# ConverterBoardRev2.net
KiCad netlist of a schematic drawn in EAGLE
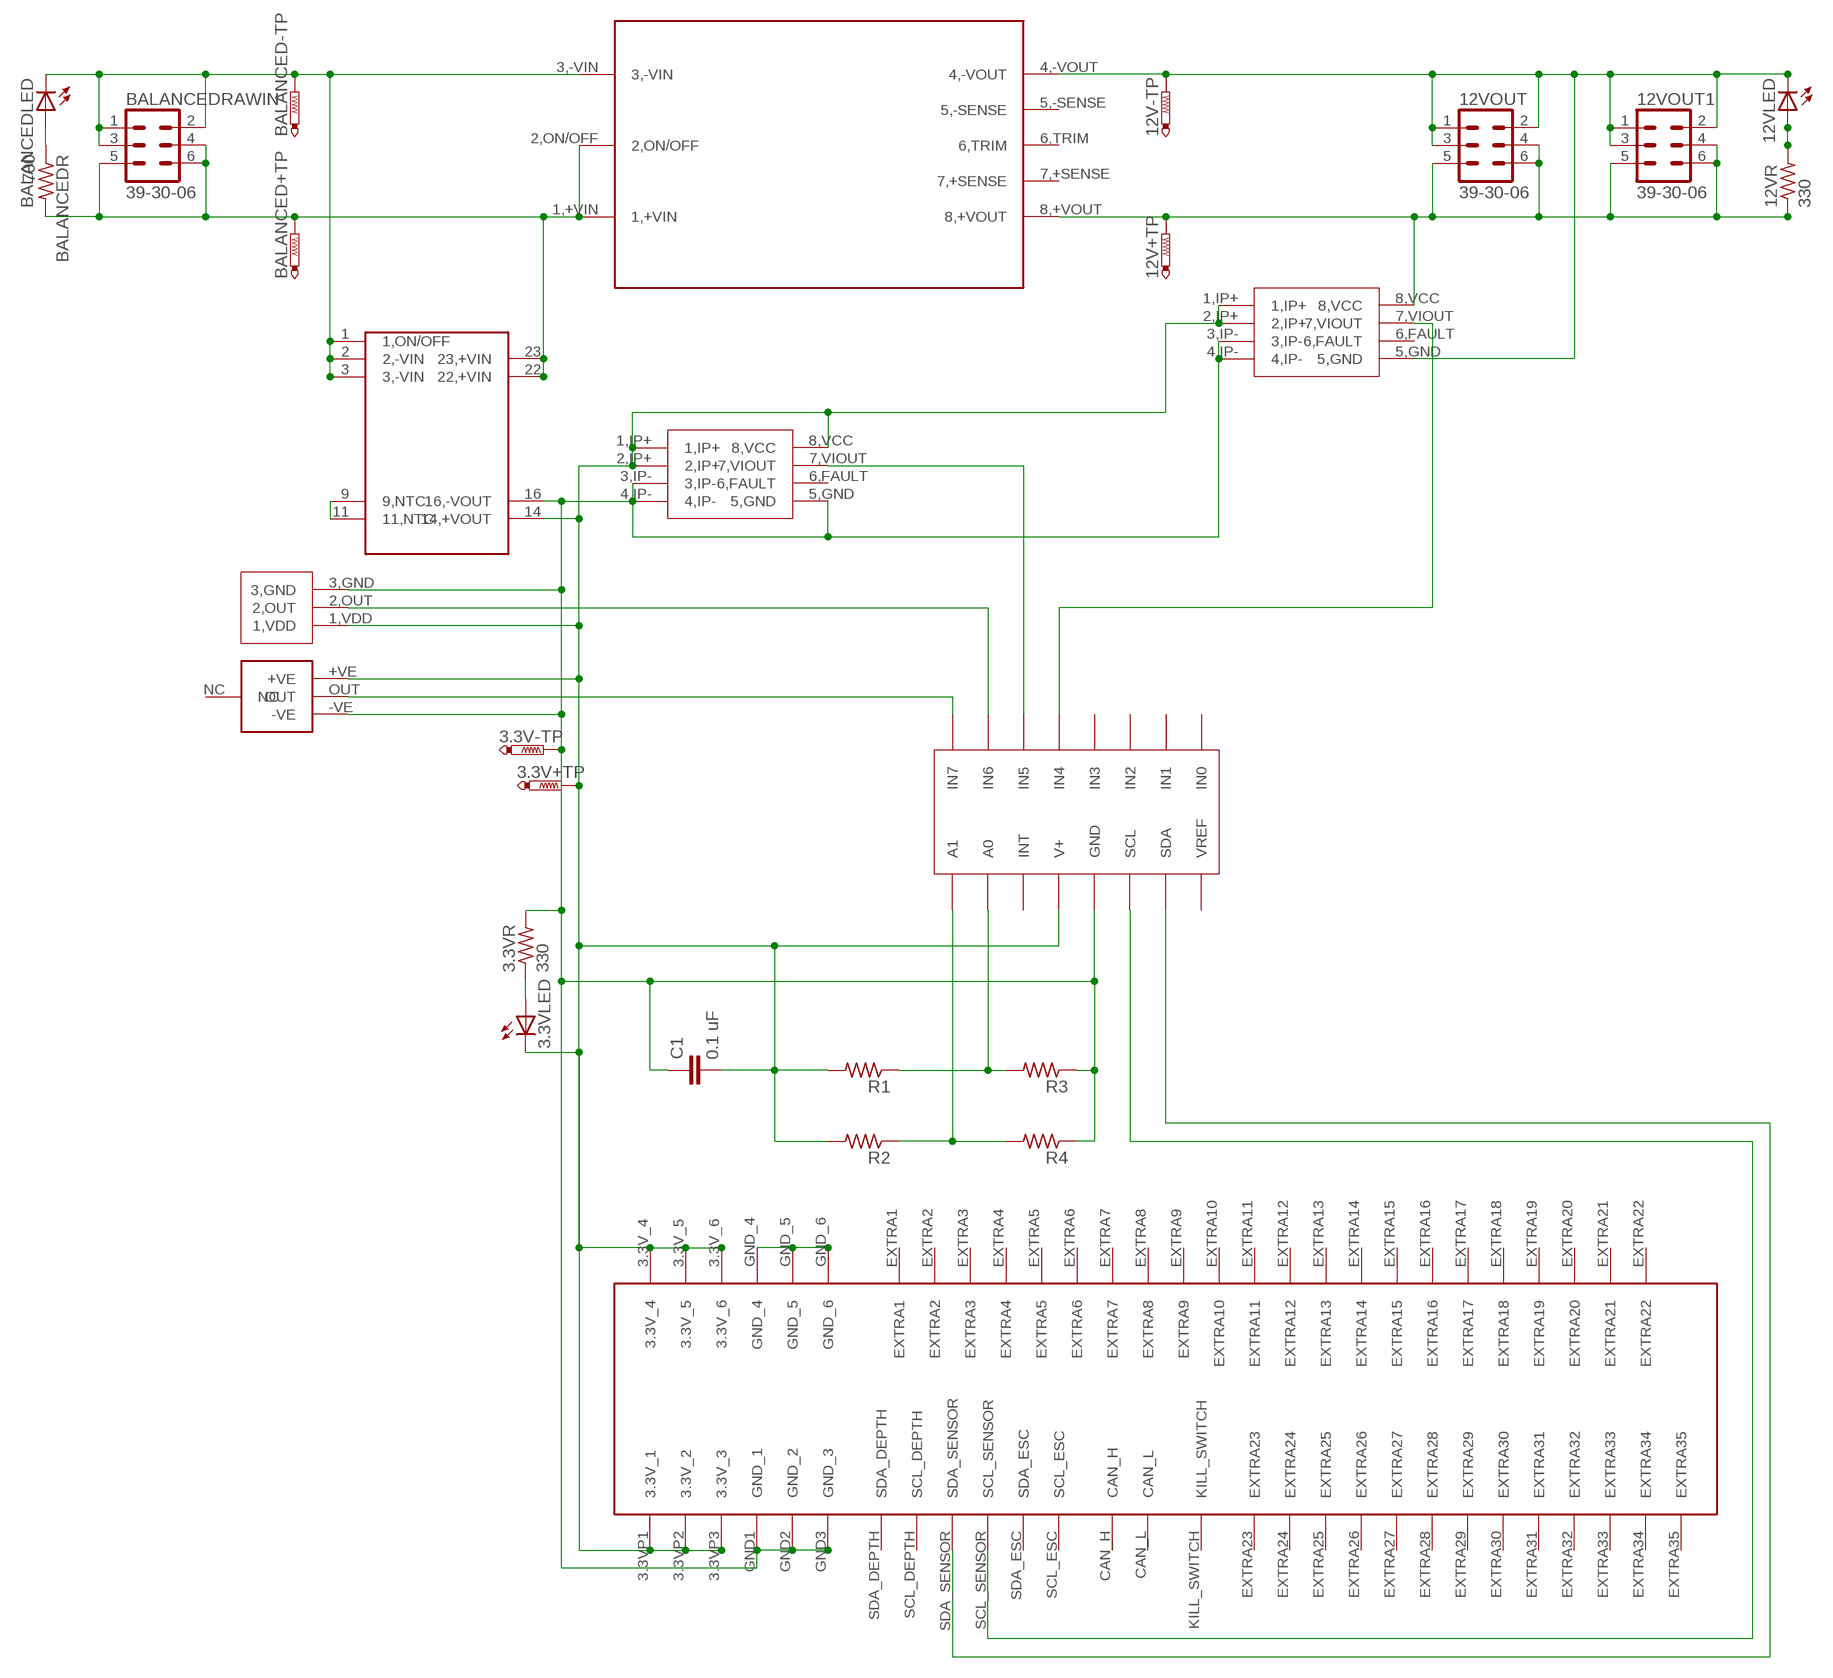
[diagram p0: schematic, sheet 1]

(export (version "E")
  (design (tool "Eeschema 10.0.6"))
  (components
    (comp (ref "3.3V+TP")
      (value "PTR1B1,27")
      (footprint "eagle-import:B1,27")
      (libsource (lib "eagle-import") (part "PTR1B1,27"))
    )
    (comp (ref "3.3V-TP")
      (value "PTR1B1,27")
      (footprint "eagle-import:B1,27")
      (libsource (lib "eagle-import") (part "PTR1B1,27"))
    )
    (comp (ref "3.3VLED")
      (value "LTST-S270GKT")
      (footprint "eagle-import:LTST-S270GKT")
      (libsource (lib "eagle-import") (part "LTST-S270GKT"))
    )
    (comp (ref "3.3VR")
      (value "330")
      (footprint "eagle-import:0204_7")
      (libsource (lib "eagle-import") (part "R-US_0204/7"))
    )
    (comp (ref "12V+TP")
      (value "PTR1B1,27")
      (footprint "eagle-import:B1,27")
      (libsource (lib "eagle-import") (part "PTR1B1,27"))
    )
    (comp (ref "12V-TP")
      (value "PTR1B1,27")
      (footprint "eagle-import:B1,27")
      (libsource (lib "eagle-import") (part "PTR1B1,27"))
    )
    (comp (ref "12VLED")
      (value "LTST-S270GKT")
      (footprint "eagle-import:LTST-S270GKT")
      (libsource (lib "eagle-import") (part "LTST-S270GKT"))
    )
    (comp (ref "12VOUT")
      (value "39-30-06")
      (footprint "eagle-import:39-30-_06_")
      (libsource (lib "eagle-import") (part "39-30-?06?"))
    )
    (comp (ref "12VOUT1")
      (value "39-30-06")
      (footprint "eagle-import:39-30-_06_")
      (libsource (lib "eagle-import") (part "39-30-?06?"))
    )
    (comp (ref "12VR")
      (value "330")
      (footprint "eagle-import:0204_7")
      (libsource (lib "eagle-import") (part "R-US_0204/7"))
    )
    (comp (ref "BALANCED+TP")
      (value "PTR1B1,27")
      (footprint "eagle-import:B1,27")
      (libsource (lib "eagle-import") (part "PTR1B1,27"))
    )
    (comp (ref "BALANCED-TP")
      (value "PTR1B1,27")
      (footprint "eagle-import:B1,27")
      (libsource (lib "eagle-import") (part "PTR1B1,27"))
    )
    (comp (ref "BALANCEDLED")
      (value "LTST-S270GKT")
      (footprint "eagle-import:LTST-S270GKT")
      (libsource (lib "eagle-import") (part "LTST-S270GKT"))
    )
    (comp (ref "BALANCEDR")
      (value "700")
      (footprint "eagle-import:0204_7")
      (libsource (lib "eagle-import") (part "R-US_0204/7"))
    )
    (comp (ref "BALANCEDRAWIN")
      (value "39-30-06")
      (footprint "eagle-import:39-30-_06_")
      (libsource (lib "eagle-import") (part "39-30-?06?"))
    )
    (comp (ref "C1")
      (value "0.1 uF")
      (footprint "eagle-import:C025-024X044")
      (libsource (lib "eagle-import") (part "C-EU025-024X044"))
    )
    (comp (ref "R1")
      (value "R-US_0204/7")
      (footprint "eagle-import:0204_7")
      (libsource (lib "eagle-import") (part "R-US_0204/7"))
    )
    (comp (ref "R2")
      (value "R-US_0204/7")
      (footprint "eagle-import:0204_7")
      (libsource (lib "eagle-import") (part "R-US_0204/7"))
    )
    (comp (ref "R3")
      (value "R-US_0204/7")
      (footprint "eagle-import:0204_7")
      (libsource (lib "eagle-import") (part "R-US_0204/7"))
    )
    (comp (ref "R4")
      (value "R-US_0204/7")
      (footprint "eagle-import:0204_7")
      (libsource (lib "eagle-import") (part "R-US_0204/7"))
    )
    (comp (ref "U$1")
      (value "12VCONV")
      (footprint "eagle-import:12VCONV")
      (libsource (lib "eagle-import") (part "12VCONV"))
    )
    (comp (ref "U$2")
      (value "3.3VCONV")
      (footprint "eagle-import:3.3VCONV")
      (libsource (lib "eagle-import") (part "3.3VCONV"))
    )
    (comp (ref "U$3")
      (value "5530843")
      (footprint "eagle-import:5530843-6-BOARDFINGERS")
      (libsource (lib "eagle-import") (part "5530843"))
    )
    (comp (ref "U$4")
      (value "CURRENTSENS")
      (footprint "eagle-import:CURRENTSENS")
      (libsource (lib "eagle-import") (part "CURRENTSENS"))
    )
    (comp (ref "U$5")
      (value "CURRENTSENS")
      (footprint "eagle-import:CURRENTSENS")
      (libsource (lib "eagle-import") (part "CURRENTSENS"))
    )
    (comp (ref "U$6")
      (value "HUMIDITYSENSOR")
      (footprint "eagle-import:HUMIDITYSENSOR")
      (libsource (lib "eagle-import") (part "HUMIDITYSENSOR"))
    )
    (comp (ref "U$7")
      (value "TEMPSENS")
      (footprint "eagle-import:TEMPSENS")
      (libsource (lib "eagle-import") (part "TEMPSENS"))
    )
    (comp (ref "U$8")
      (value "ADC128D818")
      (footprint "eagle-import:TSSOP-16")
      (libsource (lib "eagle-import") (part "ADC128D818"))
    )
  )
  (nets
    (net (code "1") (name "Net-(3.3VLED-A)") (class "Default")
      (node (ref "3.3VLED") (pin "ANODE") (pinfunction "A_ANODE") (pintype "passive"))
      (node (ref "3.3VR") (pin "1") (pinfunction "1_1") (pintype "passive"))
    )
    (net (code "2") (name "Net-(3.3VLED-C)") (class "Default")
      (node (ref "3.3V+TP") (pin "TP") (pinfunction "TP_TP") (pintype "input"))
      (node (ref "3.3VLED") (pin "CATHODE") (pinfunction "C_CATHODE") (pintype "passive"))
      (node (ref "C1") (pin "2") (pinfunction "2_2") (pintype "passive"))
      (node (ref "R1") (pin "2") (pinfunction "2_2") (pintype "passive"))
      (node (ref "R2") (pin "2") (pinfunction "2_2") (pintype "passive"))
      (node (ref "U$2") (pin "14") (pinfunction "14,+VOUT_14") (pintype "bidirectional"))
      (node (ref "U$3") (pin "3.3VP1") (pinfunction "3.3V_1_3.3VP1") (pintype "bidirectional"))
      (node (ref "U$3") (pin "3.3VP2") (pinfunction "3.3V_2_3.3VP2") (pintype "bidirectional"))
      (node (ref "U$3") (pin "3.3VP3") (pinfunction "3.3V_3_3.3VP3") (pintype "bidirectional"))
      (node (ref "U$3") (pin "3.3V_4") (pinfunction "3.3V_4_3.3V_4") (pintype "bidirectional"))
      (node (ref "U$3") (pin "3.3V_5") (pinfunction "3.3V_5_3.3V_5") (pintype "bidirectional"))
      (node (ref "U$3") (pin "3.3V_6") (pinfunction "3.3V_6_3.3V_6") (pintype "bidirectional"))
      (node (ref "U$4") (pin "1,IP+") (pinfunction "1,IP+_1,IP+") (pintype "bidirectional"))
      (node (ref "U$4") (pin "2,IP+") (pinfunction "2,IP+_2,IP+") (pintype "bidirectional"))
      (node (ref "U$5") (pin "1,IP+") (pinfunction "1,IP+_1,IP+") (pintype "bidirectional"))
      (node (ref "U$5") (pin "2,IP+") (pinfunction "2,IP+_2,IP+") (pintype "bidirectional"))
      (node (ref "U$5") (pin "8,VCC") (pinfunction "8,VCC_8,VCC") (pintype "bidirectional"))
      (node (ref "U$6") (pin "+VE") (pinfunction "+VE_+VE") (pintype "bidirectional"))
      (node (ref "U$7") (pin "1,VDD") (pinfunction "1,VDD_1,VDD") (pintype "bidirectional"))
      (node (ref "U$8") (pin "V+") (pinfunction "V+_V+") (pintype "bidirectional"))
    )
    (net (code "3") (name "Net-(12V+TP-PadTP)") (class "Default")
      (node (ref "12V+TP") (pin "TP") (pinfunction "TP_TP") (pintype "input"))
      (node (ref "12VOUT") (pin "4") (pinfunction "4_4") (pintype "passive"))
      (node (ref "12VOUT") (pin "5") (pinfunction "5_5") (pintype "passive"))
      (node (ref "12VOUT") (pin "6") (pinfunction "6_6") (pintype "passive"))
      (node (ref "12VOUT1") (pin "4") (pinfunction "4_4") (pintype "passive"))
      (node (ref "12VOUT1") (pin "5") (pinfunction "5_5") (pintype "passive"))
      (node (ref "12VOUT1") (pin "6") (pinfunction "6_6") (pintype "passive"))
      (node (ref "12VR") (pin "1") (pinfunction "1_1") (pintype "passive"))
      (node (ref "U$1") (pin "8,+VOUT") (pinfunction "8,+VOUT_8,+VOUT") (pintype "bidirectional"))
      (node (ref "U$4") (pin "8,VCC") (pinfunction "8,VCC_8,VCC") (pintype "bidirectional"))
    )
    (net (code "4") (name "Net-(12VLED-A)") (class "Default")
      (node (ref "12VLED") (pin "ANODE") (pinfunction "A_ANODE") (pintype "passive"))
      (node (ref "12VR") (pin "2") (pinfunction "2_2") (pintype "passive"))
    )
    (net (code "5") (name "Net-(12VLED-C)") (class "Default")
      (node (ref "12V-TP") (pin "TP") (pinfunction "TP_TP") (pintype "input"))
      (node (ref "12VLED") (pin "CATHODE") (pinfunction "C_CATHODE") (pintype "passive"))
      (node (ref "12VOUT") (pin "1") (pinfunction "1_1") (pintype "passive"))
      (node (ref "12VOUT") (pin "2") (pinfunction "2_2") (pintype "passive"))
      (node (ref "12VOUT") (pin "3") (pinfunction "3_3") (pintype "passive"))
      (node (ref "12VOUT1") (pin "1") (pinfunction "1_1") (pintype "passive"))
      (node (ref "12VOUT1") (pin "2") (pinfunction "2_2") (pintype "passive"))
      (node (ref "12VOUT1") (pin "3") (pinfunction "3_3") (pintype "passive"))
      (node (ref "U$1") (pin "4,-VOUT") (pinfunction "4,-VOUT_4,-VOUT") (pintype "bidirectional"))
      (node (ref "U$4") (pin "5,GND") (pinfunction "5,GND_5,GND") (pintype "bidirectional"))
    )
    (net (code "6") (name "Net-(BALANCEDLED-A)") (class "Default")
      (node (ref "BALANCEDLED") (pin "ANODE") (pinfunction "A_ANODE") (pintype "passive"))
      (node (ref "BALANCEDR") (pin "1") (pinfunction "1_1") (pintype "passive"))
    )
    (net (code "7") (name "Net-(BALANCEDLED-C)") (class "Default")
      (node (ref "BALANCED-TP") (pin "TP") (pinfunction "TP_TP") (pintype "input"))
      (node (ref "BALANCEDLED") (pin "CATHODE") (pinfunction "C_CATHODE") (pintype "passive"))
      (node (ref "BALANCEDRAWIN") (pin "1") (pinfunction "1_1") (pintype "passive"))
      (node (ref "BALANCEDRAWIN") (pin "2") (pinfunction "2_2") (pintype "passive"))
      (node (ref "BALANCEDRAWIN") (pin "3") (pinfunction "3_3") (pintype "passive"))
      (node (ref "U$1") (pin "3,-VIN") (pinfunction "3,-VIN_3,-VIN") (pintype "bidirectional"))
      (node (ref "U$2") (pin "1") (pinfunction "1,ON/OFF_1") (pintype "bidirectional"))
      (node (ref "U$2") (pin "2") (pinfunction "2,-VIN_2") (pintype "bidirectional"))
      (node (ref "U$2") (pin "3") (pinfunction "3,-VIN_3") (pintype "bidirectional"))
    )
    (net (code "8") (name "Net-(R1-Pad1)") (class "Default")
      (node (ref "R1") (pin "1") (pinfunction "1_1") (pintype "passive"))
      (node (ref "R3") (pin "2") (pinfunction "2_2") (pintype "passive"))
      (node (ref "U$8") (pin "A0") (pinfunction "A0_A0") (pintype "bidirectional"))
    )
    (net (code "9") (name "Net-(R2-Pad1)") (class "Default")
      (node (ref "R2") (pin "1") (pinfunction "1_1") (pintype "passive"))
      (node (ref "R4") (pin "2") (pinfunction "2_2") (pintype "passive"))
      (node (ref "U$8") (pin "A1") (pinfunction "A1_A1") (pintype "bidirectional"))
    )
    (net (code "10") (name "Net-(U$2-11,NTC)") (class "Default")
      (node (ref "U$2") (pin "11") (pinfunction "11,NTC_11") (pintype "bidirectional"))
      (node (ref "U$2") (pin "9") (pinfunction "9,NTC_9") (pintype "bidirectional"))
    )
    (net (code "11") (name "Net-(U$2-16,-VOUT)") (class "Default")
      (node (ref "3.3V-TP") (pin "TP") (pinfunction "TP_TP") (pintype "input"))
      (node (ref "3.3VR") (pin "2") (pinfunction "2_2") (pintype "passive"))
      (node (ref "C1") (pin "1") (pinfunction "1_1") (pintype "passive"))
      (node (ref "R3") (pin "1") (pinfunction "1_1") (pintype "passive"))
      (node (ref "R4") (pin "1") (pinfunction "1_1") (pintype "passive"))
      (node (ref "U$2") (pin "16") (pinfunction "16,-VOUT_16") (pintype "bidirectional"))
      (node (ref "U$3") (pin "GND1") (pinfunction "GND_1_GND1") (pintype "bidirectional"))
      (node (ref "U$3") (pin "GND2") (pinfunction "GND_2_GND2") (pintype "bidirectional"))
      (node (ref "U$3") (pin "GND3") (pinfunction "GND_3_GND3") (pintype "bidirectional"))
      (node (ref "U$4") (pin "3,IP-") (pinfunction "3,IP-_3,IP-") (pintype "bidirectional"))
      (node (ref "U$4") (pin "4,IP-") (pinfunction "4,IP-_4,IP-") (pintype "bidirectional"))
      (node (ref "U$5") (pin "3,IP-") (pinfunction "3,IP-_3,IP-") (pintype "bidirectional"))
      (node (ref "U$5") (pin "4,IP-") (pinfunction "4,IP-_4,IP-") (pintype "bidirectional"))
      (node (ref "U$5") (pin "5,GND") (pinfunction "5,GND_5,GND") (pintype "bidirectional"))
      (node (ref "U$6") (pin "-VE") (pinfunction "-VE_-VE") (pintype "bidirectional"))
      (node (ref "U$7") (pin "3,GND") (pinfunction "3,GND_3,GND") (pintype "bidirectional"))
      (node (ref "U$8") (pin "GND") (pinfunction "GND_GND") (pintype "bidirectional"))
    )
    (net (code "12") (name "Net-(U$2-22,+VIN)") (class "Default")
      (node (ref "BALANCED+TP") (pin "TP") (pinfunction "TP_TP") (pintype "input"))
      (node (ref "BALANCEDR") (pin "2") (pinfunction "2_2") (pintype "passive"))
      (node (ref "BALANCEDRAWIN") (pin "4") (pinfunction "4_4") (pintype "passive"))
      (node (ref "BALANCEDRAWIN") (pin "5") (pinfunction "5_5") (pintype "passive"))
      (node (ref "BALANCEDRAWIN") (pin "6") (pinfunction "6_6") (pintype "passive"))
      (node (ref "U$1") (pin "1,+VIN") (pinfunction "1,+VIN_1,+VIN") (pintype "bidirectional"))
      (node (ref "U$1") (pin "2,ON/OFF") (pinfunction "2,ON/OFF_2,ON/OFF") (pintype "bidirectional"))
      (node (ref "U$2") (pin "22") (pinfunction "22,+VIN_22") (pintype "bidirectional"))
      (node (ref "U$2") (pin "23") (pinfunction "23,+VIN_23") (pintype "bidirectional"))
    )
    (net (code "13") (name "Net-(U$3-PadGND_4)") (class "Default")
      (node (ref "U$3") (pin "GND_4") (pinfunction "GND_4_GND_4") (pintype "bidirectional"))
      (node (ref "U$3") (pin "GND_5") (pinfunction "GND_5_GND_5") (pintype "bidirectional"))
      (node (ref "U$3") (pin "GND_6") (pinfunction "GND_6_GND_6") (pintype "bidirectional"))
    )
    (net (code "14") (name "Net-(U$3-PadSCL_SENSOR)") (class "Default")
      (node (ref "U$3") (pin "SCL_SENSOR") (pinfunction "SCL_SENSOR_SCL_SENSOR") (pintype "bidirectional"))
      (node (ref "U$8") (pin "SCL") (pinfunction "SCL_SCL") (pintype "bidirectional"))
    )
    (net (code "15") (name "Net-(U$3-PadSDA_SENSOR)") (class "Default")
      (node (ref "U$3") (pin "SDA_SENSOR") (pinfunction "SDA_SENSOR_SDA_SENSOR") (pintype "bidirectional"))
      (node (ref "U$8") (pin "SDA") (pinfunction "SDA_SDA") (pintype "bidirectional"))
    )
    (net (code "16") (name "Net-(U$4-Pad7,VIOUT)") (class "Default")
      (node (ref "U$4") (pin "7,VIOUT") (pinfunction "7,VIOUT_7,VIOUT") (pintype "bidirectional"))
      (node (ref "U$8") (pin "IN4") (pinfunction "IN4_IN4") (pintype "bidirectional"))
    )
    (net (code "17") (name "Net-(U$5-Pad7,VIOUT)") (class "Default")
      (node (ref "U$5") (pin "7,VIOUT") (pinfunction "7,VIOUT_7,VIOUT") (pintype "bidirectional"))
      (node (ref "U$8") (pin "IN5") (pinfunction "IN5_IN5") (pintype "bidirectional"))
    )
    (net (code "18") (name "Net-(U$6-PadOUT)") (class "Default")
      (node (ref "U$6") (pin "OUT") (pinfunction "OUT_OUT") (pintype "bidirectional"))
      (node (ref "U$8") (pin "IN7") (pinfunction "IN7_IN7") (pintype "bidirectional"))
    )
    (net (code "19") (name "Net-(U$7-Pad2,OUT)") (class "Default")
      (node (ref "U$7") (pin "2,OUT") (pinfunction "2,OUT_2,OUT") (pintype "bidirectional"))
      (node (ref "U$8") (pin "IN6") (pinfunction "IN6_IN6") (pintype "bidirectional"))
    )
    (net (code "20") (name "unconnected-(U$1-Pad5,-SENSE)") (class "Default")
      (node (ref "U$1") (pin "5,-SENSE") (pinfunction "5,-SENSE_5,-SENSE") (pintype "bidirectional"))
    )
    (net (code "21") (name "unconnected-(U$1-Pad6,TRIM)") (class "Default")
      (node (ref "U$1") (pin "6,TRIM") (pinfunction "6,TRIM_6,TRIM") (pintype "bidirectional"))
    )
    (net (code "22") (name "unconnected-(U$1-Pad7,+SENSE)") (class "Default")
      (node (ref "U$1") (pin "7,+SENSE") (pinfunction "7,+SENSE_7,+SENSE") (pintype "bidirectional"))
    )
    (net (code "23") (name "unconnected-(U$3-PadCAN_H)") (class "Default")
      (node (ref "U$3") (pin "CAN_H") (pinfunction "CAN_H_CAN_H") (pintype "bidirectional"))
    )
    (net (code "24") (name "unconnected-(U$3-PadCAN_L)") (class "Default")
      (node (ref "U$3") (pin "CAN_L") (pinfunction "CAN_L_CAN_L") (pintype "bidirectional"))
    )
    (net (code "25") (name "unconnected-(U$3-PadEXTRA1)") (class "Default")
      (node (ref "U$3") (pin "EXTRA1") (pinfunction "EXTRA1_EXTRA1") (pintype "bidirectional"))
    )
    (net (code "26") (name "unconnected-(U$3-PadEXTRA2)") (class "Default")
      (node (ref "U$3") (pin "EXTRA2") (pinfunction "EXTRA2_EXTRA2") (pintype "bidirectional"))
    )
    (net (code "27") (name "unconnected-(U$3-PadEXTRA3)") (class "Default")
      (node (ref "U$3") (pin "EXTRA3") (pinfunction "EXTRA3_EXTRA3") (pintype "bidirectional"))
    )
    (net (code "28") (name "unconnected-(U$3-PadEXTRA4)") (class "Default")
      (node (ref "U$3") (pin "EXTRA4") (pinfunction "EXTRA4_EXTRA4") (pintype "bidirectional"))
    )
    (net (code "29") (name "unconnected-(U$3-PadEXTRA5)") (class "Default")
      (node (ref "U$3") (pin "EXTRA5") (pinfunction "EXTRA5_EXTRA5") (pintype "bidirectional"))
    )
    (net (code "30") (name "unconnected-(U$3-PadEXTRA6)") (class "Default")
      (node (ref "U$3") (pin "EXTRA6") (pinfunction "EXTRA6_EXTRA6") (pintype "bidirectional"))
    )
    (net (code "31") (name "unconnected-(U$3-PadEXTRA7)") (class "Default")
      (node (ref "U$3") (pin "EXTRA7") (pinfunction "EXTRA7_EXTRA7") (pintype "bidirectional"))
    )
    (net (code "32") (name "unconnected-(U$3-PadEXTRA8)") (class "Default")
      (node (ref "U$3") (pin "EXTRA8") (pinfunction "EXTRA8_EXTRA8") (pintype "bidirectional"))
    )
    (net (code "33") (name "unconnected-(U$3-PadEXTRA9)") (class "Default")
      (node (ref "U$3") (pin "EXTRA9") (pinfunction "EXTRA9_EXTRA9") (pintype "bidirectional"))
    )
    (net (code "34") (name "unconnected-(U$3-PadEXTRA10)") (class "Default")
      (node (ref "U$3") (pin "EXTRA10") (pinfunction "EXTRA10_EXTRA10") (pintype "bidirectional"))
    )
    (net (code "35") (name "unconnected-(U$3-PadEXTRA11)") (class "Default")
      (node (ref "U$3") (pin "EXTRA11") (pinfunction "EXTRA11_EXTRA11") (pintype "bidirectional"))
    )
    (net (code "36") (name "unconnected-(U$3-PadEXTRA12)") (class "Default")
      (node (ref "U$3") (pin "EXTRA12") (pinfunction "EXTRA12_EXTRA12") (pintype "bidirectional"))
    )
    (net (code "37") (name "unconnected-(U$3-PadEXTRA13)") (class "Default")
      (node (ref "U$3") (pin "EXTRA13") (pinfunction "EXTRA13_EXTRA13") (pintype "bidirectional"))
    )
    (net (code "38") (name "unconnected-(U$3-PadEXTRA14)") (class "Default")
      (node (ref "U$3") (pin "EXTRA14") (pinfunction "EXTRA14_EXTRA14") (pintype "bidirectional"))
    )
    (net (code "39") (name "unconnected-(U$3-PadEXTRA15)") (class "Default")
      (node (ref "U$3") (pin "EXTRA15") (pinfunction "EXTRA15_EXTRA15") (pintype "bidirectional"))
    )
    (net (code "40") (name "unconnected-(U$3-PadEXTRA16)") (class "Default")
      (node (ref "U$3") (pin "EXTRA16") (pinfunction "EXTRA16_EXTRA16") (pintype "bidirectional"))
    )
    (net (code "41") (name "unconnected-(U$3-PadEXTRA17)") (class "Default")
      (node (ref "U$3") (pin "EXTRA17") (pinfunction "EXTRA17_EXTRA17") (pintype "bidirectional"))
    )
    (net (code "42") (name "unconnected-(U$3-PadEXTRA18)") (class "Default")
      (node (ref "U$3") (pin "EXTRA18") (pinfunction "EXTRA18_EXTRA18") (pintype "bidirectional"))
    )
    (net (code "43") (name "unconnected-(U$3-PadEXTRA19)") (class "Default")
      (node (ref "U$3") (pin "EXTRA19") (pinfunction "EXTRA19_EXTRA19") (pintype "bidirectional"))
    )
    (net (code "44") (name "unconnected-(U$3-PadEXTRA20)") (class "Default")
      (node (ref "U$3") (pin "EXTRA20") (pinfunction "EXTRA20_EXTRA20") (pintype "bidirectional"))
    )
    (net (code "45") (name "unconnected-(U$3-PadEXTRA21)") (class "Default")
      (node (ref "U$3") (pin "EXTRA21") (pinfunction "EXTRA21_EXTRA21") (pintype "bidirectional"))
    )
    (net (code "46") (name "unconnected-(U$3-PadEXTRA22)") (class "Default")
      (node (ref "U$3") (pin "EXTRA22") (pinfunction "EXTRA22_EXTRA22") (pintype "bidirectional"))
    )
    (net (code "47") (name "unconnected-(U$3-PadEXTRA23)") (class "Default")
      (node (ref "U$3") (pin "EXTRA23") (pinfunction "EXTRA23_EXTRA23") (pintype "bidirectional"))
    )
    (net (code "48") (name "unconnected-(U$3-PadEXTRA24)") (class "Default")
      (node (ref "U$3") (pin "EXTRA24") (pinfunction "EXTRA24_EXTRA24") (pintype "bidirectional"))
    )
    (net (code "49") (name "unconnected-(U$3-PadEXTRA25)") (class "Default")
      (node (ref "U$3") (pin "EXTRA25") (pinfunction "EXTRA25_EXTRA25") (pintype "bidirectional"))
    )
    (net (code "50") (name "unconnected-(U$3-PadEXTRA26)") (class "Default")
      (node (ref "U$3") (pin "EXTRA26") (pinfunction "EXTRA26_EXTRA26") (pintype "bidirectional"))
    )
    (net (code "51") (name "unconnected-(U$3-PadEXTRA27)") (class "Default")
      (node (ref "U$3") (pin "EXTRA27") (pinfunction "EXTRA27_EXTRA27") (pintype "bidirectional"))
    )
    (net (code "52") (name "unconnected-(U$3-PadEXTRA28)") (class "Default")
      (node (ref "U$3") (pin "EXTRA28") (pinfunction "EXTRA28_EXTRA28") (pintype "bidirectional"))
    )
    (net (code "53") (name "unconnected-(U$3-PadEXTRA29)") (class "Default")
      (node (ref "U$3") (pin "EXTRA29") (pinfunction "EXTRA29_EXTRA29") (pintype "bidirectional"))
    )
    (net (code "54") (name "unconnected-(U$3-PadEXTRA30)") (class "Default")
      (node (ref "U$3") (pin "EXTRA30") (pinfunction "EXTRA30_EXTRA30") (pintype "bidirectional"))
    )
    (net (code "55") (name "unconnected-(U$3-PadEXTRA31)") (class "Default")
      (node (ref "U$3") (pin "EXTRA31") (pinfunction "EXTRA31_EXTRA31") (pintype "bidirectional"))
    )
    (net (code "56") (name "unconnected-(U$3-PadEXTRA32)") (class "Default")
      (node (ref "U$3") (pin "EXTRA32") (pinfunction "EXTRA32_EXTRA32") (pintype "bidirectional"))
    )
    (net (code "57") (name "unconnected-(U$3-PadEXTRA33)") (class "Default")
      (node (ref "U$3") (pin "EXTRA33") (pinfunction "EXTRA33_EXTRA33") (pintype "bidirectional"))
    )
    (net (code "58") (name "unconnected-(U$3-PadEXTRA34)") (class "Default")
      (node (ref "U$3") (pin "EXTRA34") (pinfunction "EXTRA34_EXTRA34") (pintype "bidirectional"))
    )
    (net (code "59") (name "unconnected-(U$3-PadEXTRA35)") (class "Default")
      (node (ref "U$3") (pin "EXTRA35") (pinfunction "EXTRA35_EXTRA35") (pintype "bidirectional"))
    )
    (net (code "60") (name "unconnected-(U$3-PadKILL_SWITCH)") (class "Default")
      (node (ref "U$3") (pin "KILL_SWITCH") (pinfunction "KILL_SWITCH_KILL_SWITCH") (pintype "bidirectional"))
    )
    (net (code "61") (name "unconnected-(U$3-PadSCL_DEPTH)") (class "Default")
      (node (ref "U$3") (pin "SCL_DEPTH") (pinfunction "SCL_DEPTH_SCL_DEPTH") (pintype "bidirectional"))
    )
    (net (code "62") (name "unconnected-(U$3-PadSCL_ESC)") (class "Default")
      (node (ref "U$3") (pin "SCL_ESC") (pinfunction "SCL_ESC_SCL_ESC") (pintype "bidirectional"))
    )
    (net (code "63") (name "unconnected-(U$3-PadSDA_DEPTH)") (class "Default")
      (node (ref "U$3") (pin "SDA_DEPTH") (pinfunction "SDA_DEPTH_SDA_DEPTH") (pintype "bidirectional"))
    )
    (net (code "64") (name "unconnected-(U$3-PadSDA_ESC)") (class "Default")
      (node (ref "U$3") (pin "SDA_ESC") (pinfunction "SDA_ESC_SDA_ESC") (pintype "bidirectional"))
    )
    (net (code "65") (name "unconnected-(U$4-Pad6,FAULT)") (class "Default")
      (node (ref "U$4") (pin "6,FAULT") (pinfunction "6,FAULT_6,FAULT") (pintype "bidirectional"))
    )
    (net (code "66") (name "unconnected-(U$5-Pad6,FAULT)") (class "Default")
      (node (ref "U$5") (pin "6,FAULT") (pinfunction "6,FAULT_6,FAULT") (pintype "bidirectional"))
    )
    (net (code "67") (name "unconnected-(U$6-PadNC)") (class "Default")
      (node (ref "U$6") (pin "NC") (pinfunction "NC_NC") (pintype "bidirectional"))
    )
    (net (code "68") (name "unconnected-(U$8-PadIN0)") (class "Default")
      (node (ref "U$8") (pin "IN0") (pinfunction "IN0_IN0") (pintype "bidirectional"))
    )
    (net (code "69") (name "unconnected-(U$8-PadIN1)") (class "Default")
      (node (ref "U$8") (pin "IN1") (pinfunction "IN1_IN1") (pintype "bidirectional"))
    )
    (net (code "70") (name "unconnected-(U$8-PadIN2)") (class "Default")
      (node (ref "U$8") (pin "IN2") (pinfunction "IN2_IN2") (pintype "bidirectional"))
    )
    (net (code "71") (name "unconnected-(U$8-PadIN3)") (class "Default")
      (node (ref "U$8") (pin "IN3") (pinfunction "IN3_IN3") (pintype "bidirectional"))
    )
    (net (code "72") (name "unconnected-(U$8-PadINT)") (class "Default")
      (node (ref "U$8") (pin "INT") (pinfunction "INT_INT") (pintype "bidirectional"))
    )
    (net (code "73") (name "unconnected-(U$8-PadVREF)") (class "Default")
      (node (ref "U$8") (pin "VREF") (pinfunction "VREF_VREF") (pintype "bidirectional"))
    )
  )
)
